# PAGE06_FPGA_Power.net
KiCad netlist of a schematic drawn in Altium Designer
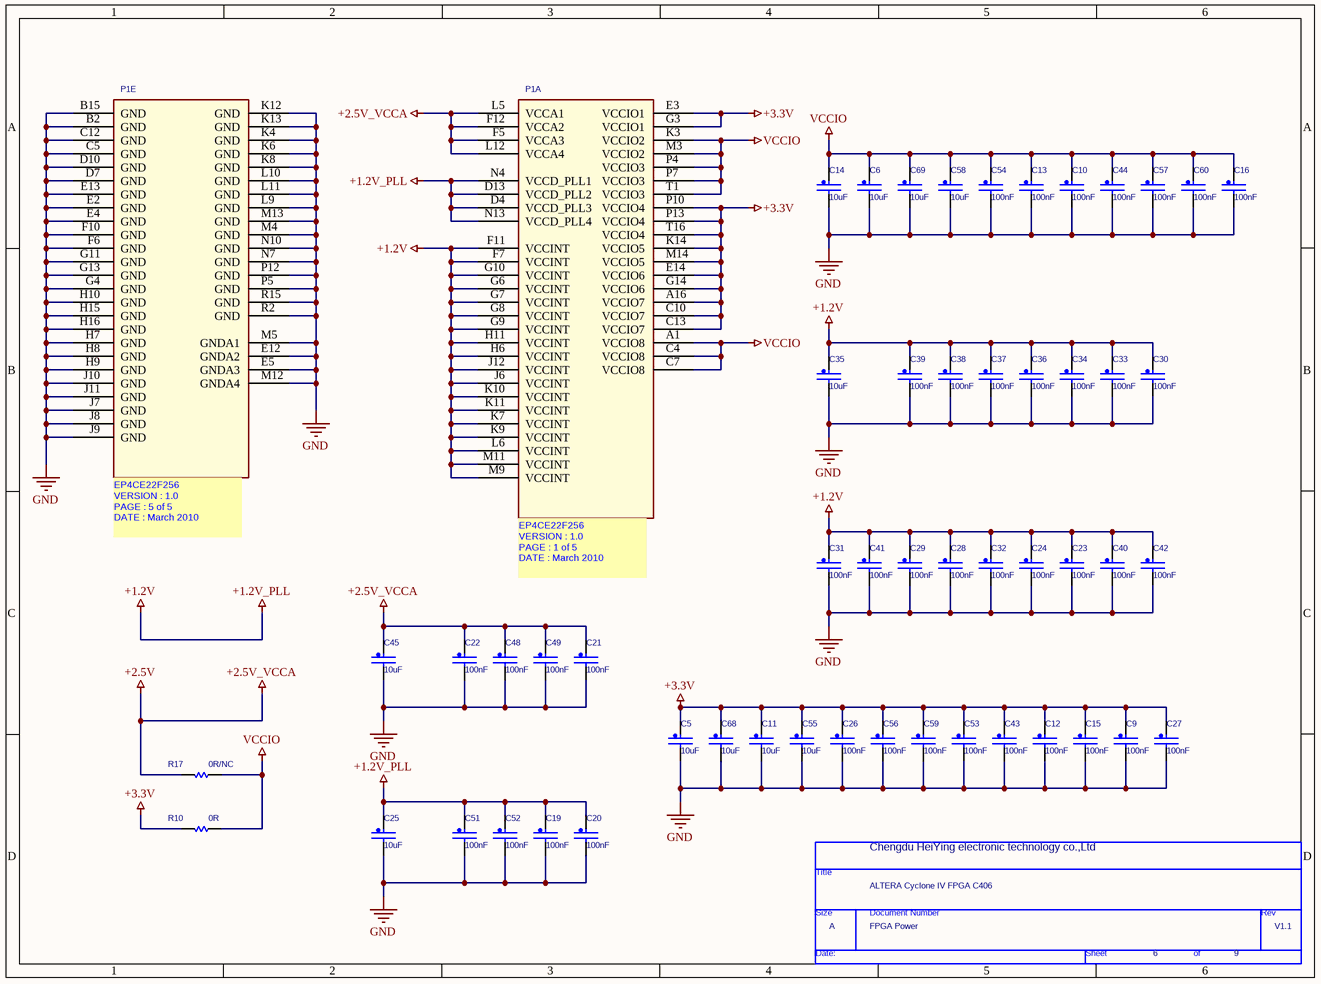
[diagram p0: PAGE06 FPGA Power.SchDoc]

(export (version "E")
  (design (tool "Eeschema 10.0.6"))
  (components
    (comp (ref "C5")
      (value "10uF")
      (description "Capacitor, 10u, 0805, X6S, 10%, 10V")
      (fields (field (name "TOLERANCE") "10%"))
      (libsource (lib "*") (part "CAP_NP"))
    )
    (comp (ref "C6")
      (value "10uF")
      (description "Capacitor, 10u, 0805, X6S, 10%, 10V")
      (fields (field (name "TOLERANCE") "10%"))
      (libsource (lib "*") (part "CAP_NP"))
    )
    (comp (ref "C9")
      (value "100nF")
      (description "CAP CER 0.1UF 6.3V 10% X5R 0201")
      (fields (field (name "TOLERANCE") "10%"))
      (libsource (lib "*") (part "CAP_NP"))
    )
    (comp (ref "C10")
      (value "100nF")
      (description "CAP CER 0.1UF 6.3V 10% X5R 0201")
      (fields (field (name "TOLERANCE") "10%"))
      (libsource (lib "*") (part "CAP_NP"))
    )
    (comp (ref "C11")
      (value "10uF")
      (description "Capacitor, 10u, 0805, X6S, 10%, 10V")
      (fields (field (name "TOLERANCE") "10%"))
      (libsource (lib "*") (part "CAP_NP"))
    )
    (comp (ref "C12")
      (value "100nF")
      (description "CAP CER 0.1UF 6.3V 10% X5R 0201")
      (fields (field (name "TOLERANCE") "10%"))
      (libsource (lib "*") (part "CAP_NP"))
    )
    (comp (ref "C13")
      (value "100nF")
      (description "CAP CER 0.1UF 6.3V 10% X5R 0201")
      (fields (field (name "TOLERANCE") "10%"))
      (libsource (lib "*") (part "CAP_NP"))
    )
    (comp (ref "C14")
      (value "10uF")
      (description "Capacitor, 10u, 0805, X6S, 10%, 10V")
      (fields (field (name "TOLERANCE") "10%"))
      (libsource (lib "*") (part "CAP_NP"))
    )
    (comp (ref "C15")
      (value "100nF")
      (description "CAP CER 0.1UF 6.3V 10% X5R 0201")
      (fields (field (name "TOLERANCE") "10%"))
      (libsource (lib "*") (part "CAP_NP"))
    )
    (comp (ref "C16")
      (value "100nF")
      (description "CAP CER 0.1UF 6.3V 10% X5R 0201")
      (fields (field (name "TOLERANCE") "10%"))
      (libsource (lib "*") (part "CAP_NP"))
    )
    (comp (ref "C19")
      (value "100nF")
      (description "CAP CER 0.1UF 6.3V 10% X5R 0201")
      (fields (field (name "TOLERANCE") "10%"))
      (libsource (lib "*") (part "CAP_NP"))
    )
    (comp (ref "C20")
      (value "100nF")
      (description "CAP CER 0.1UF 6.3V 10% X5R 0201")
      (fields (field (name "TOLERANCE") "10%"))
      (libsource (lib "*") (part "CAP_NP"))
    )
    (comp (ref "C21")
      (value "100nF")
      (description "CAP CER 0.1UF 6.3V 10% X5R 0201")
      (fields (field (name "TOLERANCE") "10%"))
      (libsource (lib "*") (part "CAP_NP"))
    )
    (comp (ref "C22")
      (value "100nF")
      (description "CAP CER 0.1UF 6.3V 10% X5R 0201")
      (fields (field (name "TOLERANCE") "10%"))
      (libsource (lib "*") (part "CAP_NP"))
    )
    (comp (ref "C23")
      (value "100nF")
      (description "CAP CER 0.1UF 6.3V 10% X5R 0201")
      (fields (field (name "TOLERANCE") "10%"))
      (libsource (lib "*") (part "CAP_NP"))
    )
    (comp (ref "C24")
      (value "100nF")
      (description "CAP CER 0.1UF 6.3V 10% X5R 0201")
      (fields (field (name "TOLERANCE") "10%"))
      (libsource (lib "*") (part "CAP_NP"))
    )
    (comp (ref "C25")
      (value "10uF")
      (description "Capacitor, 10u, 0805, X6S, 10%, 10V")
      (fields (field (name "TOLERANCE") "10%"))
      (libsource (lib "*") (part "CAP_NP"))
    )
    (comp (ref "C26")
      (value "100nF")
      (description "CAP CER 0.1UF 6.3V 10% X5R 0201")
      (fields (field (name "TOLERANCE") "10%"))
      (libsource (lib "*") (part "CAP_NP"))
    )
    (comp (ref "C27")
      (value "100nF")
      (description "CAP CER 0.1UF 6.3V 10% X5R 0201")
      (fields (field (name "TOLERANCE") "10%"))
      (libsource (lib "*") (part "CAP_NP"))
    )
    (comp (ref "C28")
      (value "100nF")
      (description "CAP CER 0.1UF 6.3V 10% X5R 0201")
      (fields (field (name "TOLERANCE") "10%"))
      (libsource (lib "*") (part "CAP_NP"))
    )
    (comp (ref "C29")
      (value "100nF")
      (description "CAP CER 0.1UF 6.3V 10% X5R 0201")
      (fields (field (name "TOLERANCE") "10%"))
      (libsource (lib "*") (part "CAP_NP"))
    )
    (comp (ref "C30")
      (value "100nF")
      (description "CAP CER 0.1UF 6.3V 10% X5R 0201")
      (fields (field (name "TOLERANCE") "10%"))
      (libsource (lib "*") (part "CAP_NP"))
    )
    (comp (ref "C31")
      (value "100nF")
      (description "CAP CER 0.1UF 6.3V 10% X5R 0201")
      (fields (field (name "TOLERANCE") "10%"))
      (libsource (lib "*") (part "CAP_NP"))
    )
    (comp (ref "C32")
      (value "100nF")
      (description "CAP CER 0.1UF 6.3V 10% X5R 0201")
      (fields (field (name "TOLERANCE") "10%"))
      (libsource (lib "*") (part "CAP_NP"))
    )
    (comp (ref "C33")
      (value "100nF")
      (description "CAP CER 0.1UF 6.3V 10% X5R 0201")
      (fields (field (name "TOLERANCE") "10%"))
      (libsource (lib "*") (part "CAP_NP"))
    )
    (comp (ref "C34")
      (value "100nF")
      (description "CAP CER 0.1UF 6.3V 10% X5R 0201")
      (fields (field (name "TOLERANCE") "10%"))
      (libsource (lib "*") (part "CAP_NP"))
    )
    (comp (ref "C35")
      (value "10uF")
      (description "Capacitor, 10u, 0805, X6S, 10%, 10V")
      (fields (field (name "TOLERANCE") "10%"))
      (libsource (lib "*") (part "CAP_NP"))
    )
    (comp (ref "C36")
      (value "100nF")
      (description "CAP CER 0.1UF 6.3V 10% X5R 0201")
      (fields (field (name "TOLERANCE") "10%"))
      (libsource (lib "*") (part "CAP_NP"))
    )
    (comp (ref "C37")
      (value "100nF")
      (description "CAP CER 0.1UF 6.3V 10% X5R 0201")
      (fields (field (name "TOLERANCE") "10%"))
      (libsource (lib "*") (part "CAP_NP"))
    )
    (comp (ref "C38")
      (value "100nF")
      (description "CAP CER 0.1UF 6.3V 10% X5R 0201")
      (fields (field (name "TOLERANCE") "10%"))
      (libsource (lib "*") (part "CAP_NP"))
    )
    (comp (ref "C39")
      (value "100nF")
      (description "CAP CER 0.1UF 6.3V 10% X5R 0201")
      (fields (field (name "TOLERANCE") "10%"))
      (libsource (lib "*") (part "CAP_NP"))
    )
    (comp (ref "C40")
      (value "100nF")
      (description "CAP CER 0.1UF 6.3V 10% X5R 0201")
      (fields (field (name "TOLERANCE") "10%"))
      (libsource (lib "*") (part "CAP_NP"))
    )
    (comp (ref "C41")
      (value "100nF")
      (description "CAP CER 0.1UF 6.3V 10% X5R 0201")
      (fields (field (name "TOLERANCE") "10%"))
      (libsource (lib "*") (part "CAP_NP"))
    )
    (comp (ref "C42")
      (value "100nF")
      (description "CAP CER 0.1UF 6.3V 10% X5R 0201")
      (fields (field (name "TOLERANCE") "10%"))
      (libsource (lib "*") (part "CAP_NP"))
    )
    (comp (ref "C43")
      (value "100nF")
      (description "CAP CER 0.1UF 6.3V 10% X5R 0201")
      (fields (field (name "TOLERANCE") "10%"))
      (libsource (lib "*") (part "CAP_NP"))
    )
    (comp (ref "C44")
      (value "100nF")
      (description "CAP CER 0.1UF 6.3V 10% X5R 0201")
      (fields (field (name "TOLERANCE") "10%"))
      (libsource (lib "*") (part "CAP_NP"))
    )
    (comp (ref "C45")
      (value "10uF")
      (description "Capacitor, 10u, 0805, X6S, 10%, 10V")
      (fields (field (name "TOLERANCE") "10%"))
      (libsource (lib "*") (part "CAP_NP"))
    )
    (comp (ref "C48")
      (value "100nF")
      (description "CAP CER 0.1UF 6.3V 10% X5R 0201")
      (fields (field (name "TOLERANCE") "10%"))
      (libsource (lib "*") (part "CAP_NP"))
    )
    (comp (ref "C49")
      (value "100nF")
      (description "CAP CER 0.1UF 6.3V 10% X5R 0201")
      (fields (field (name "TOLERANCE") "10%"))
      (libsource (lib "*") (part "CAP_NP"))
    )
    (comp (ref "C51")
      (value "100nF")
      (description "CAP CER 0.1UF 6.3V 10% X5R 0201")
      (fields (field (name "TOLERANCE") "10%"))
      (libsource (lib "*") (part "CAP_NP"))
    )
    (comp (ref "C52")
      (value "100nF")
      (description "CAP CER 0.1UF 6.3V 10% X5R 0201")
      (fields (field (name "TOLERANCE") "10%"))
      (libsource (lib "*") (part "CAP_NP"))
    )
    (comp (ref "C53")
      (value "100nF")
      (description "CAP CER 0.1UF 6.3V 10% X5R 0201")
      (fields (field (name "TOLERANCE") "10%"))
      (libsource (lib "*") (part "CAP_NP"))
    )
    (comp (ref "C54")
      (value "100nF")
      (description "CAP CER 0.1UF 6.3V 10% X5R 0201")
      (fields (field (name "TOLERANCE") "10%"))
      (libsource (lib "*") (part "CAP_NP"))
    )
    (comp (ref "C55")
      (value "10uF")
      (description "Capacitor, 10u, 0805, X6S, 10%, 10V")
      (fields (field (name "TOLERANCE") "10%"))
      (libsource (lib "*") (part "CAP_NP"))
    )
    (comp (ref "C56")
      (value "100nF")
      (description "CAP CER 0.1UF 6.3V 10% X5R 0201")
      (fields (field (name "TOLERANCE") "10%"))
      (libsource (lib "*") (part "CAP_NP"))
    )
    (comp (ref "C57")
      (value "100nF")
      (description "CAP CER 0.1UF 6.3V 10% X5R 0201")
      (fields (field (name "TOLERANCE") "10%"))
      (libsource (lib "*") (part "CAP_NP"))
    )
    (comp (ref "C58")
      (value "10uF")
      (description "Capacitor, 10u, 0805, X6S, 10%, 10V")
      (fields (field (name "TOLERANCE") "10%"))
      (libsource (lib "*") (part "CAP_NP"))
    )
    (comp (ref "C59")
      (value "100nF")
      (description "CAP CER 0.1UF 6.3V 10% X5R 0201")
      (fields (field (name "TOLERANCE") "10%"))
      (libsource (lib "*") (part "CAP_NP"))
    )
    (comp (ref "C60")
      (value "100nF")
      (description "CAP CER 0.1UF 6.3V 10% X5R 0201")
      (fields (field (name "TOLERANCE") "10%"))
      (libsource (lib "*") (part "CAP_NP"))
    )
    (comp (ref "C68")
      (value "10uF")
      (description "Capacitor, 10u, 0805, X6S, 10%, 10V")
      (fields (field (name "TOLERANCE") "10%"))
      (libsource (lib "*") (part "CAP_NP"))
    )
    (comp (ref "C69")
      (value "10uF")
      (description "Capacitor, 10u, 0805, X6S, 10%, 10V")
      (fields (field (name "TOLERANCE") "10%"))
      (libsource (lib "*") (part "CAP_NP"))
    )
    (comp (ref "P1") (value "EP4CE22F256") (libsource (lib "*") (part "EP4CE22F256")))
    (comp (ref "R10") (value "0R") (libsource (lib "*") (part "SMALL R1")))
    (comp (ref "R17") (value "0R/NC") (libsource (lib "*") (part "SMALL R1")))
  )
  (nets
    (net (code "1") (name "+1.2V") (class "Default")
      (node (ref "C19") (pin "1") (pinfunction "1_1") (pintype "passive"))
      (node (ref "C20") (pin "1") (pinfunction "1_1") (pintype "passive"))
      (node (ref "C23") (pin "1") (pinfunction "1_1") (pintype "passive"))
      (node (ref "C24") (pin "1") (pinfunction "1_1") (pintype "passive"))
      (node (ref "C25") (pin "1") (pinfunction "1_1") (pintype "passive"))
      (node (ref "C28") (pin "1") (pinfunction "1_1") (pintype "passive"))
      (node (ref "C29") (pin "1") (pinfunction "1_1") (pintype "passive"))
      (node (ref "C30") (pin "1") (pinfunction "1_1") (pintype "passive"))
      (node (ref "C31") (pin "1") (pinfunction "1_1") (pintype "passive"))
      (node (ref "C32") (pin "1") (pinfunction "1_1") (pintype "passive"))
      (node (ref "C33") (pin "1") (pinfunction "1_1") (pintype "passive"))
      (node (ref "C34") (pin "1") (pinfunction "1_1") (pintype "passive"))
      (node (ref "C35") (pin "1") (pinfunction "1_1") (pintype "passive"))
      (node (ref "C36") (pin "1") (pinfunction "1_1") (pintype "passive"))
      (node (ref "C37") (pin "1") (pinfunction "1_1") (pintype "passive"))
      (node (ref "C38") (pin "1") (pinfunction "1_1") (pintype "passive"))
      (node (ref "C39") (pin "1") (pinfunction "1_1") (pintype "passive"))
      (node (ref "C40") (pin "1") (pinfunction "1_1") (pintype "passive"))
      (node (ref "C41") (pin "1") (pinfunction "1_1") (pintype "passive"))
      (node (ref "C42") (pin "1") (pinfunction "1_1") (pintype "passive"))
      (node (ref "C51") (pin "1") (pinfunction "1_1") (pintype "passive"))
      (node (ref "C52") (pin "1") (pinfunction "1_1") (pintype "passive"))
      (node (ref "P1") (pin "D13") (pinfunction "VCCD_PLL2_D13") (pintype "power_in"))
      (node (ref "P1") (pin "D4") (pinfunction "VCCD_PLL3_D4") (pintype "power_in"))
      (node (ref "P1") (pin "F11") (pinfunction "VCCINT_F11") (pintype "power_in"))
      (node (ref "P1") (pin "F7") (pinfunction "VCCINT_F7") (pintype "power_in"))
      (node (ref "P1") (pin "G10") (pinfunction "VCCINT_G10") (pintype "power_in"))
      (node (ref "P1") (pin "G6") (pinfunction "VCCINT_G6") (pintype "power_in"))
      (node (ref "P1") (pin "G7") (pinfunction "VCCINT_G7") (pintype "power_in"))
      (node (ref "P1") (pin "G8") (pinfunction "VCCINT_G8") (pintype "power_in"))
      (node (ref "P1") (pin "G9") (pinfunction "VCCINT_G9") (pintype "power_in"))
      (node (ref "P1") (pin "H11") (pinfunction "VCCINT_H11") (pintype "power_in"))
      (node (ref "P1") (pin "H6") (pinfunction "VCCINT_H6") (pintype "power_in"))
      (node (ref "P1") (pin "J12") (pinfunction "VCCINT_J12") (pintype "power_in"))
      (node (ref "P1") (pin "J6") (pinfunction "VCCINT_J6") (pintype "power_in"))
      (node (ref "P1") (pin "K10") (pinfunction "VCCINT_K10") (pintype "power_in"))
      (node (ref "P1") (pin "K11") (pinfunction "VCCINT_K11") (pintype "power_in"))
      (node (ref "P1") (pin "K7") (pinfunction "VCCINT_K7") (pintype "power_in"))
      (node (ref "P1") (pin "K9") (pinfunction "VCCINT_K9") (pintype "power_in"))
      (node (ref "P1") (pin "L6") (pinfunction "VCCINT_L6") (pintype "power_in"))
      (node (ref "P1") (pin "M11") (pinfunction "VCCINT_M11") (pintype "power_in"))
      (node (ref "P1") (pin "M9") (pinfunction "VCCINT_M9") (pintype "power_in"))
      (node (ref "P1") (pin "N13") (pinfunction "VCCD_PLL4_N13") (pintype "power_in"))
      (node (ref "P1") (pin "N4") (pinfunction "VCCD_PLL1_N4") (pintype "power_in"))
    )
    (net (code "2") (name "+2.5V") (class "Default")
      (node (ref "C21") (pin "1") (pinfunction "1_1") (pintype "passive"))
      (node (ref "C22") (pin "1") (pinfunction "1_1") (pintype "passive"))
      (node (ref "C45") (pin "1") (pinfunction "1_1") (pintype "passive"))
      (node (ref "C48") (pin "1") (pinfunction "1_1") (pintype "passive"))
      (node (ref "C49") (pin "1") (pinfunction "1_1") (pintype "passive"))
      (node (ref "P1") (pin "F12") (pinfunction "VCCA2_F12") (pintype "power_in"))
      (node (ref "P1") (pin "F5") (pinfunction "VCCA3_F5") (pintype "power_in"))
      (node (ref "P1") (pin "L12") (pinfunction "VCCA4_L12") (pintype "power_in"))
      (node (ref "P1") (pin "L5") (pinfunction "VCCA1_L5") (pintype "power_in"))
      (node (ref "R17") (pin "2") (pinfunction "2_2") (pintype "passive"))
    )
    (net (code "3") (name "+3.3V") (class "Default")
      (node (ref "C11") (pin "1") (pinfunction "1_1") (pintype "passive"))
      (node (ref "C12") (pin "1") (pinfunction "1_1") (pintype "passive"))
      (node (ref "C15") (pin "1") (pinfunction "1_1") (pintype "passive"))
      (node (ref "C26") (pin "1") (pinfunction "1_1") (pintype "passive"))
      (node (ref "C27") (pin "1") (pinfunction "1_1") (pintype "passive"))
      (node (ref "C43") (pin "1") (pinfunction "1_1") (pintype "passive"))
      (node (ref "C5") (pin "1") (pinfunction "1_1") (pintype "passive"))
      (node (ref "C53") (pin "1") (pinfunction "1_1") (pintype "passive"))
      (node (ref "C55") (pin "1") (pinfunction "1_1") (pintype "passive"))
      (node (ref "C56") (pin "1") (pinfunction "1_1") (pintype "passive"))
      (node (ref "C59") (pin "1") (pinfunction "1_1") (pintype "passive"))
      (node (ref "C68") (pin "1") (pinfunction "1_1") (pintype "passive"))
      (node (ref "C9") (pin "1") (pinfunction "1_1") (pintype "passive"))
      (node (ref "P1") (pin "A16") (pinfunction "VCCIO7_A16") (pintype "power_in"))
      (node (ref "P1") (pin "C10") (pinfunction "VCCIO7_C10") (pintype "power_in"))
      (node (ref "P1") (pin "C13") (pinfunction "VCCIO7_C13") (pintype "power_in"))
      (node (ref "P1") (pin "E14") (pinfunction "VCCIO6_E14") (pintype "power_in"))
      (node (ref "P1") (pin "E3") (pinfunction "VCCIO1_E3") (pintype "power_in"))
      (node (ref "P1") (pin "G14") (pinfunction "VCCIO6_G14") (pintype "power_in"))
      (node (ref "P1") (pin "G3") (pinfunction "VCCIO1_G3") (pintype "power_in"))
      (node (ref "P1") (pin "K14") (pinfunction "VCCIO5_K14") (pintype "power_in"))
      (node (ref "P1") (pin "M14") (pinfunction "VCCIO5_M14") (pintype "power_in"))
      (node (ref "P1") (pin "P10") (pinfunction "VCCIO4_P10") (pintype "power_in"))
      (node (ref "P1") (pin "P13") (pinfunction "VCCIO4_P13") (pintype "power_in"))
      (node (ref "P1") (pin "T16") (pinfunction "VCCIO4_T16") (pintype "power_in"))
      (node (ref "R10") (pin "2") (pinfunction "2_2") (pintype "passive"))
    )
    (net (code "4") (name "GND") (class "Default")
      (node (ref "C10") (pin "2") (pinfunction "2_2") (pintype "passive"))
      (node (ref "C11") (pin "2") (pinfunction "2_2") (pintype "passive"))
      (node (ref "C12") (pin "2") (pinfunction "2_2") (pintype "passive"))
      (node (ref "C13") (pin "2") (pinfunction "2_2") (pintype "passive"))
      (node (ref "C14") (pin "2") (pinfunction "2_2") (pintype "passive"))
      (node (ref "C15") (pin "2") (pinfunction "2_2") (pintype "passive"))
      (node (ref "C16") (pin "2") (pinfunction "2_2") (pintype "passive"))
      (node (ref "C19") (pin "2") (pinfunction "2_2") (pintype "passive"))
      (node (ref "C20") (pin "2") (pinfunction "2_2") (pintype "passive"))
      (node (ref "C21") (pin "2") (pinfunction "2_2") (pintype "passive"))
      (node (ref "C22") (pin "2") (pinfunction "2_2") (pintype "passive"))
      (node (ref "C23") (pin "2") (pinfunction "2_2") (pintype "passive"))
      (node (ref "C24") (pin "2") (pinfunction "2_2") (pintype "passive"))
      (node (ref "C25") (pin "2") (pinfunction "2_2") (pintype "passive"))
      (node (ref "C26") (pin "2") (pinfunction "2_2") (pintype "passive"))
      (node (ref "C27") (pin "2") (pinfunction "2_2") (pintype "passive"))
      (node (ref "C28") (pin "2") (pinfunction "2_2") (pintype "passive"))
      (node (ref "C29") (pin "2") (pinfunction "2_2") (pintype "passive"))
      (node (ref "C30") (pin "2") (pinfunction "2_2") (pintype "passive"))
      (node (ref "C31") (pin "2") (pinfunction "2_2") (pintype "passive"))
      (node (ref "C32") (pin "2") (pinfunction "2_2") (pintype "passive"))
      (node (ref "C33") (pin "2") (pinfunction "2_2") (pintype "passive"))
      (node (ref "C34") (pin "2") (pinfunction "2_2") (pintype "passive"))
      (node (ref "C35") (pin "2") (pinfunction "2_2") (pintype "passive"))
      (node (ref "C36") (pin "2") (pinfunction "2_2") (pintype "passive"))
      (node (ref "C37") (pin "2") (pinfunction "2_2") (pintype "passive"))
      (node (ref "C38") (pin "2") (pinfunction "2_2") (pintype "passive"))
      (node (ref "C39") (pin "2") (pinfunction "2_2") (pintype "passive"))
      (node (ref "C40") (pin "2") (pinfunction "2_2") (pintype "passive"))
      (node (ref "C41") (pin "2") (pinfunction "2_2") (pintype "passive"))
      (node (ref "C42") (pin "2") (pinfunction "2_2") (pintype "passive"))
      (node (ref "C43") (pin "2") (pinfunction "2_2") (pintype "passive"))
      (node (ref "C44") (pin "2") (pinfunction "2_2") (pintype "passive"))
      (node (ref "C45") (pin "2") (pinfunction "2_2") (pintype "passive"))
      (node (ref "C48") (pin "2") (pinfunction "2_2") (pintype "passive"))
      (node (ref "C49") (pin "2") (pinfunction "2_2") (pintype "passive"))
      (node (ref "C5") (pin "2") (pinfunction "2_2") (pintype "passive"))
      (node (ref "C51") (pin "2") (pinfunction "2_2") (pintype "passive"))
      (node (ref "C52") (pin "2") (pinfunction "2_2") (pintype "passive"))
      (node (ref "C53") (pin "2") (pinfunction "2_2") (pintype "passive"))
      (node (ref "C54") (pin "2") (pinfunction "2_2") (pintype "passive"))
      (node (ref "C55") (pin "2") (pinfunction "2_2") (pintype "passive"))
      (node (ref "C56") (pin "2") (pinfunction "2_2") (pintype "passive"))
      (node (ref "C57") (pin "2") (pinfunction "2_2") (pintype "passive"))
      (node (ref "C58") (pin "2") (pinfunction "2_2") (pintype "passive"))
      (node (ref "C59") (pin "2") (pinfunction "2_2") (pintype "passive"))
      (node (ref "C6") (pin "2") (pinfunction "2_2") (pintype "passive"))
      (node (ref "C60") (pin "2") (pinfunction "2_2") (pintype "passive"))
      (node (ref "C68") (pin "2") (pinfunction "2_2") (pintype "passive"))
      (node (ref "C69") (pin "2") (pinfunction "2_2") (pintype "passive"))
      (node (ref "C9") (pin "2") (pinfunction "2_2") (pintype "passive"))
      (node (ref "P1") (pin "B15") (pinfunction "GND_B15") (pintype "power_in"))
      (node (ref "P1") (pin "B2") (pinfunction "GND_B2") (pintype "power_in"))
      (node (ref "P1") (pin "C12") (pinfunction "GND_C12") (pintype "power_in"))
      (node (ref "P1") (pin "C5") (pinfunction "GND_C5") (pintype "power_in"))
      (node (ref "P1") (pin "D10") (pinfunction "GND_D10") (pintype "power_in"))
      (node (ref "P1") (pin "D7") (pinfunction "GND_D7") (pintype "power_in"))
      (node (ref "P1") (pin "E12") (pinfunction "GNDA2_E12") (pintype "power_in"))
      (node (ref "P1") (pin "E13") (pinfunction "GND_E13") (pintype "power_in"))
      (node (ref "P1") (pin "E2") (pinfunction "GND_E2") (pintype "power_in"))
      (node (ref "P1") (pin "E4") (pinfunction "GND_E4") (pintype "power_in"))
      (node (ref "P1") (pin "E5") (pinfunction "GNDA3_E5") (pintype "power_in"))
      (node (ref "P1") (pin "F10") (pinfunction "GND_F10") (pintype "power_in"))
      (node (ref "P1") (pin "F6") (pinfunction "GND_F6") (pintype "power_in"))
      (node (ref "P1") (pin "G11") (pinfunction "GND_G11") (pintype "power_in"))
      (node (ref "P1") (pin "G13") (pinfunction "GND_G13") (pintype "power_in"))
      (node (ref "P1") (pin "G4") (pinfunction "GND_G4") (pintype "power_in"))
      (node (ref "P1") (pin "H10") (pinfunction "GND_H10") (pintype "power_in"))
      (node (ref "P1") (pin "H15") (pinfunction "GND_H15") (pintype "power_in"))
      (node (ref "P1") (pin "H16") (pinfunction "GND_H16") (pintype "power_in"))
      (node (ref "P1") (pin "H7") (pinfunction "GND_H7") (pintype "power_in"))
      (node (ref "P1") (pin "H8") (pinfunction "GND_H8") (pintype "power_in"))
      (node (ref "P1") (pin "H9") (pinfunction "GND_H9") (pintype "power_in"))
      (node (ref "P1") (pin "J10") (pinfunction "GND_J10") (pintype "power_in"))
      (node (ref "P1") (pin "J11") (pinfunction "GND_J11") (pintype "power_in"))
      (node (ref "P1") (pin "J7") (pinfunction "GND_J7") (pintype "power_in"))
      (node (ref "P1") (pin "J8") (pinfunction "GND_J8") (pintype "power_in"))
      (node (ref "P1") (pin "J9") (pinfunction "GND_J9") (pintype "power_in"))
      (node (ref "P1") (pin "K12") (pinfunction "GND_K12") (pintype "power_in"))
      (node (ref "P1") (pin "K13") (pinfunction "GND_K13") (pintype "power_in"))
      (node (ref "P1") (pin "K4") (pinfunction "GND_K4") (pintype "power_in"))
      (node (ref "P1") (pin "K6") (pinfunction "GND_K6") (pintype "power_in"))
      (node (ref "P1") (pin "K8") (pinfunction "GND_K8") (pintype "power_in"))
      (node (ref "P1") (pin "L10") (pinfunction "GND_L10") (pintype "power_in"))
      (node (ref "P1") (pin "L11") (pinfunction "GND_L11") (pintype "power_in"))
      (node (ref "P1") (pin "L9") (pinfunction "GND_L9") (pintype "power_in"))
      (node (ref "P1") (pin "M12") (pinfunction "GNDA4_M12") (pintype "power_in"))
      (node (ref "P1") (pin "M13") (pinfunction "GND_M13") (pintype "power_in"))
      (node (ref "P1") (pin "M4") (pinfunction "GND_M4") (pintype "power_in"))
      (node (ref "P1") (pin "M5") (pinfunction "GNDA1_M5") (pintype "power_in"))
      (node (ref "P1") (pin "N10") (pinfunction "GND_N10") (pintype "power_in"))
      (node (ref "P1") (pin "N7") (pinfunction "GND_N7") (pintype "power_in"))
      (node (ref "P1") (pin "P12") (pinfunction "GND_P12") (pintype "power_in"))
      (node (ref "P1") (pin "P5") (pinfunction "GND_P5") (pintype "power_in"))
      (node (ref "P1") (pin "R15") (pinfunction "GND_R15") (pintype "power_in"))
      (node (ref "P1") (pin "R2") (pinfunction "GND_R2") (pintype "power_in"))
    )
    (net (code "5") (name "VCCIO") (class "Default")
      (node (ref "C10") (pin "1") (pinfunction "1_1") (pintype "passive"))
      (node (ref "C13") (pin "1") (pinfunction "1_1") (pintype "passive"))
      (node (ref "C14") (pin "1") (pinfunction "1_1") (pintype "passive"))
      (node (ref "C16") (pin "1") (pinfunction "1_1") (pintype "passive"))
      (node (ref "C44") (pin "1") (pinfunction "1_1") (pintype "passive"))
      (node (ref "C54") (pin "1") (pinfunction "1_1") (pintype "passive"))
      (node (ref "C57") (pin "1") (pinfunction "1_1") (pintype "passive"))
      (node (ref "C58") (pin "1") (pinfunction "1_1") (pintype "passive"))
      (node (ref "C6") (pin "1") (pinfunction "1_1") (pintype "passive"))
      (node (ref "C60") (pin "1") (pinfunction "1_1") (pintype "passive"))
      (node (ref "C69") (pin "1") (pinfunction "1_1") (pintype "passive"))
      (node (ref "P1") (pin "A1") (pinfunction "VCCIO8_A1") (pintype "power_in"))
      (node (ref "P1") (pin "C4") (pinfunction "VCCIO8_C4") (pintype "power_in"))
      (node (ref "P1") (pin "C7") (pinfunction "VCCIO8_C7") (pintype "power_in"))
      (node (ref "P1") (pin "K3") (pinfunction "VCCIO2_K3") (pintype "power_in"))
      (node (ref "P1") (pin "M3") (pinfunction "VCCIO2_M3") (pintype "power_in"))
      (node (ref "P1") (pin "P4") (pinfunction "VCCIO3_P4") (pintype "power_in"))
      (node (ref "P1") (pin "P7") (pinfunction "VCCIO3_P7") (pintype "power_in"))
      (node (ref "P1") (pin "T1") (pinfunction "VCCIO3_T1") (pintype "power_in"))
      (node (ref "R10") (pin "1") (pinfunction "1_1") (pintype "passive"))
      (node (ref "R17") (pin "1") (pinfunction "1_1") (pintype "passive"))
    )
  )
)
